# Power.net
KiCad netlist of a schematic drawn in Altium Designer
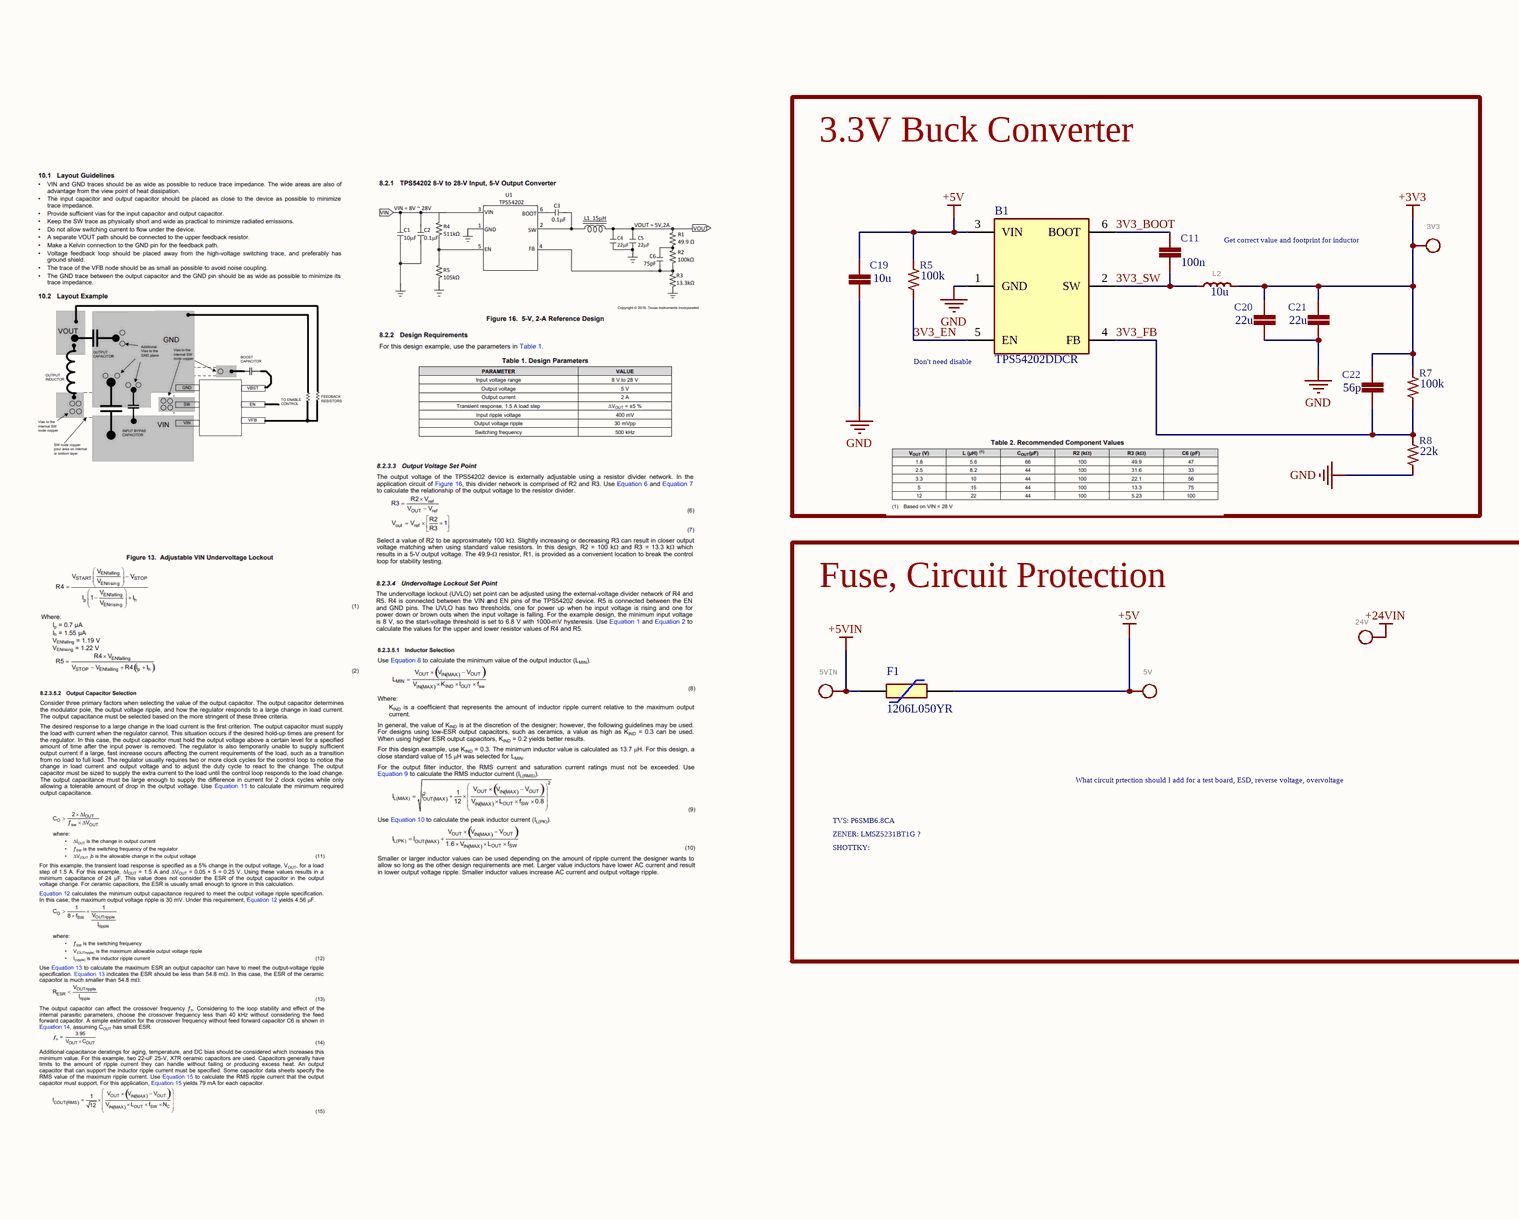
[diagram p0: Power.SchDoc, left]
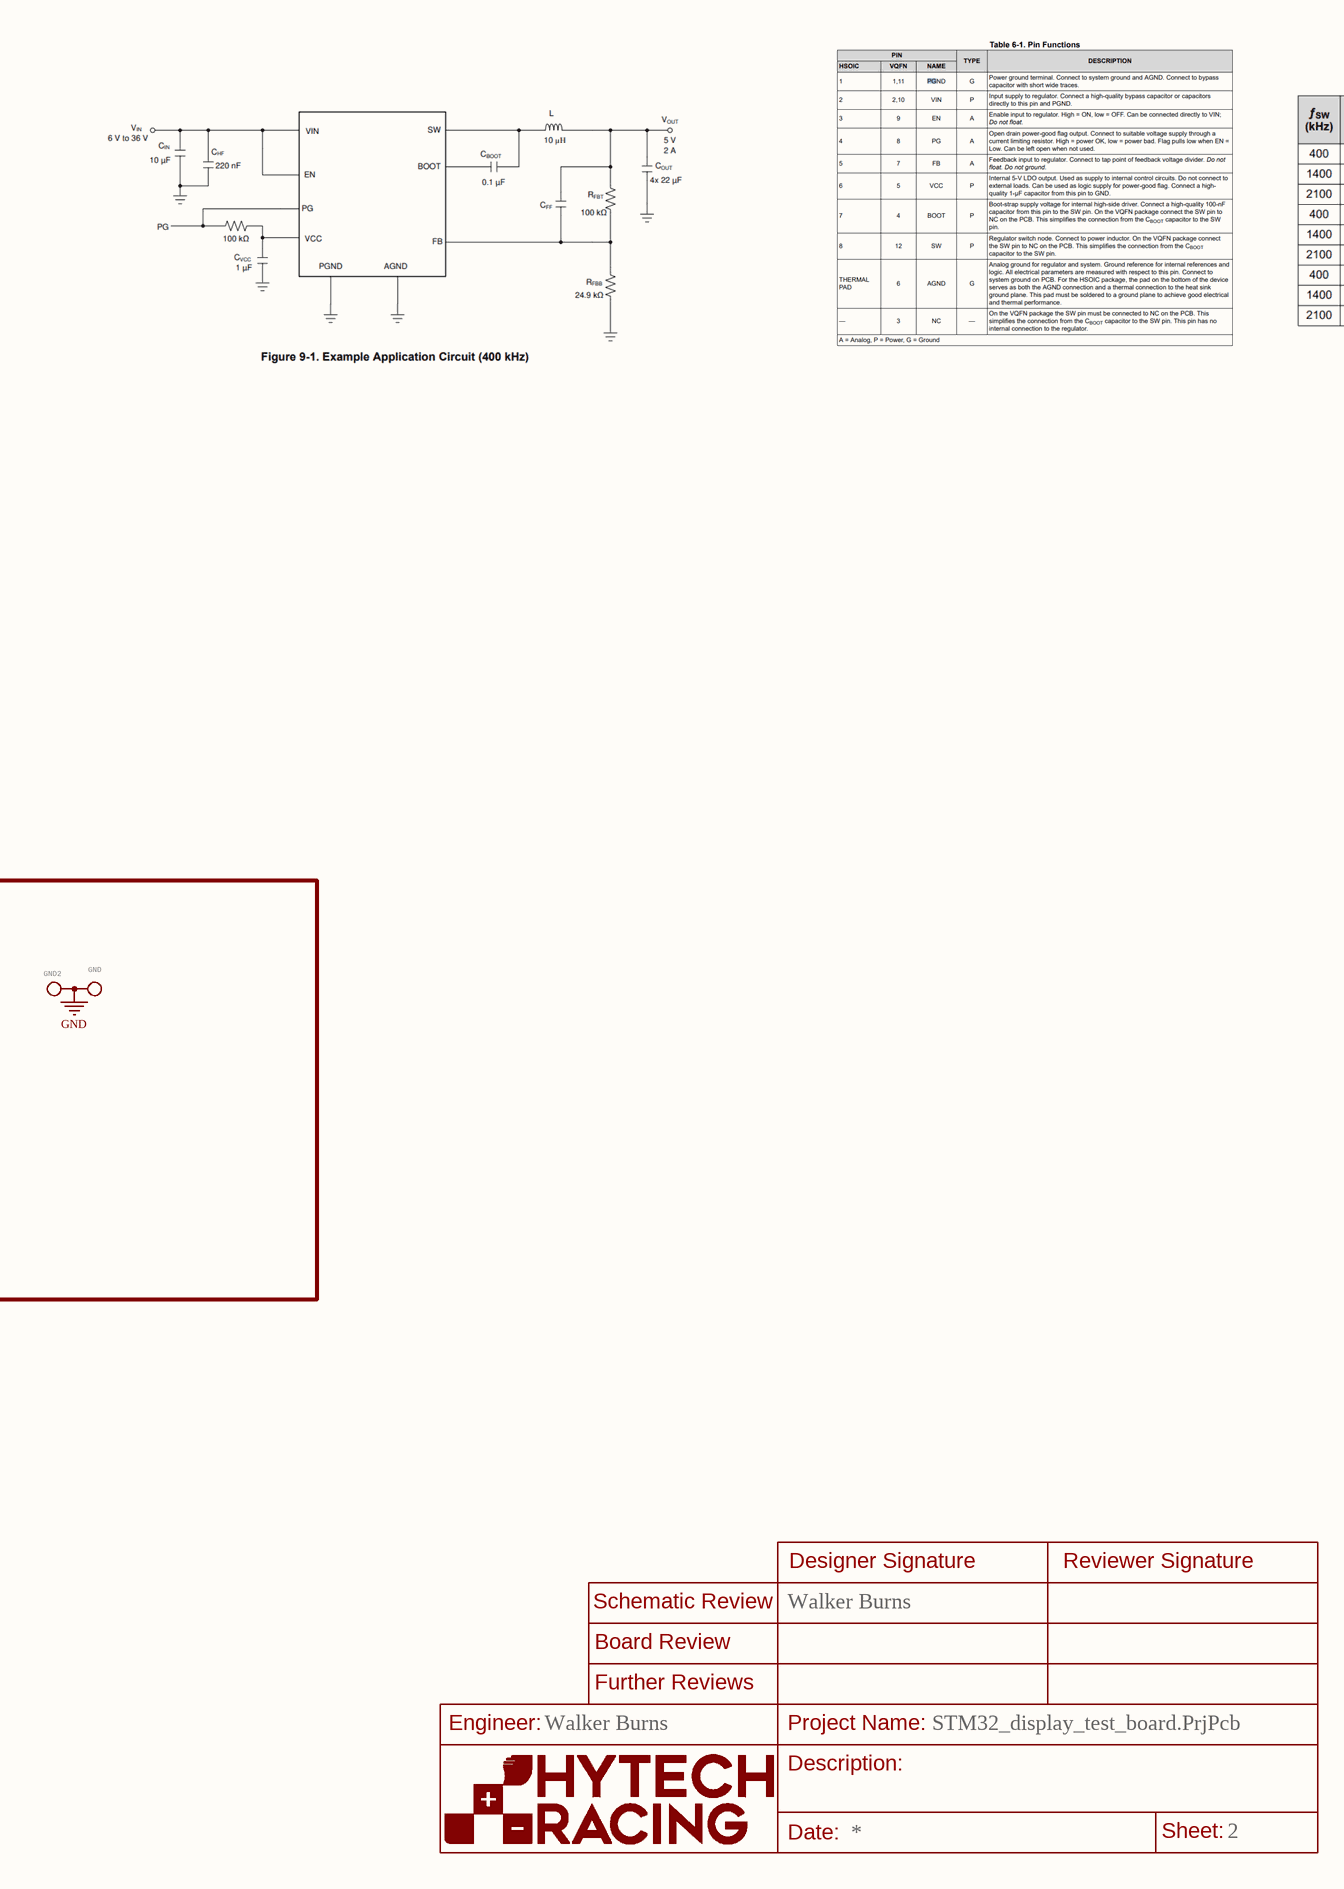
[diagram p1: Power.SchDoc, middle]
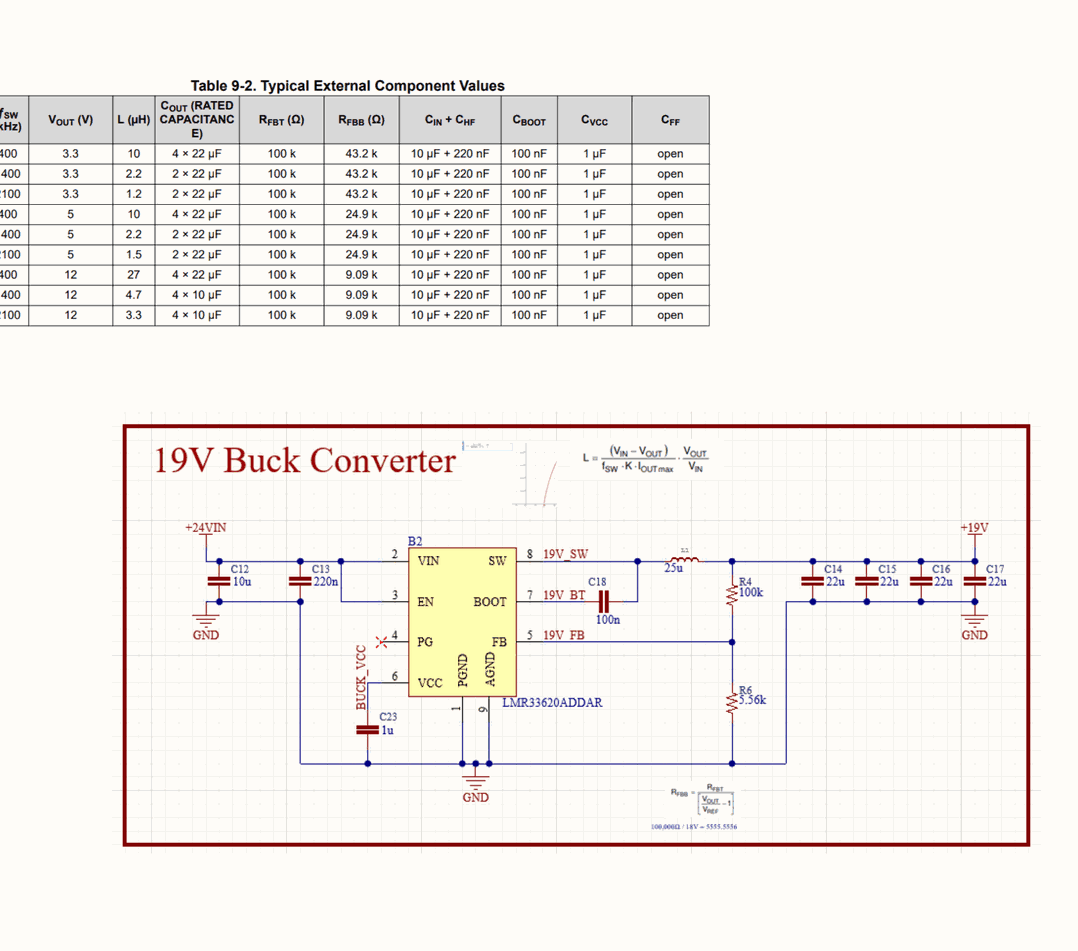
[diagram p2: Power.SchDoc, right]

(export (version "E")
  (design (tool "Eeschema 10.0.6"))
  (components
    (comp (ref "3V3")
      (value "Test Point for Probing")
      (footprint "5015")
      (fields (field (name "MANUFACTURER") "Keystone Electronics") (field (name "MPN") "5015"))
      (libsource (lib "HyTechDevices") (part "TEST_POINT"))
    )
    (comp (ref "5V")
      (value "Test Point for Probing")
      (footprint "5015")
      (fields (field (name "MANUFACTURER") "Keystone Electronics") (field (name "MPN") "5015"))
      (libsource (lib "HyTechDevices") (part "TEST_POINT"))
    )
    (comp (ref "5VIN")
      (value "Test Point for Probing")
      (footprint "5015")
      (fields (field (name "MANUFACTURER") "Keystone Electronics") (field (name "MPN") "5015"))
      (libsource (lib "HyTechDevices") (part "TEST_POINT"))
    )
    (comp (ref "24V")
      (value "Test Point for Probing")
      (footprint "5015")
      (fields (field (name "MANUFACTURER") "Keystone Electronics") (field (name "MPN") "5015"))
      (libsource (lib "HyTechDevices") (part "TEST_POINT"))
    )
    (comp (ref "B1")
      (value "TPS54202DDCR")
      (footprint "SOT-23-6")
      (description "4.5V to 28V Input, 2A Output, EMI Friendly Synchronous Step-Down Converter")
      (fields (field (name "MOUSER PART NUMBER") "595-TPS54202DDCR"))
      (libsource (lib "HyTechDevices") (part "TPS54202DDCR"))
    )
    (comp (ref "C11")
      (value "100n")
      (footprint "0402_CAP")
      (fields
        (field (name "MANUFACTURER") "Yageo")
        (field (name "MPN") "CC0603KRX7R0BB104")
        (field (name "TOLERANCE") "10%")
      )
      (libsource (lib "HyTechDevices") (part "CAPACITOR_?_*0402"))
    )
    (comp (ref "C19")
      (value "10u")
      (footprint "0805-CAP")
      (fields
        (field (name "MANUFACTURER") "KEMET")
        (field (name "MPN") "C0805C224K1RACTU")
        (field (name "TOLERANCE") "10%")
      )
      (libsource (lib "HyTechDevices") (part "CAPACITOR_?_*0805"))
    )
    (comp (ref "C20")
      (value "22u")
      (footprint "1206-CAP")
      (fields
        (field (name "MANUFACTURER") "AVX Corporation")
        (field (name "MPN") "12061C225K4T2A")
        (field (name "TOLERANCE") "10%")
      )
      (libsource (lib "HyTechDevices") (part "CAPACITOR_?_*1206"))
    )
    (comp (ref "C21")
      (value "22u")
      (footprint "1206-CAP")
      (fields
        (field (name "MANUFACTURER") "AVX Corporation")
        (field (name "MPN") "12061C225K4T2A")
        (field (name "TOLERANCE") "10%")
      )
      (libsource (lib "HyTechDevices") (part "CAPACITOR_?_*1206"))
    )
    (comp (ref "C22")
      (value "56p")
      (footprint "1206-CAP")
      (fields
        (field (name "MANUFACTURER") "AVX Corporation")
        (field (name "MPN") "12061C225K4T2A")
        (field (name "TOLERANCE") "10%")
      )
      (libsource (lib "HyTechDevices") (part "CAPACITOR_?_*1206"))
    )
    (comp (ref "F1")
      (value "1206L050YR")
      (footprint "1206-FUSE")
      (description "Resettable POLYFUSE 100A 6V Littelfuse 0.5A Surface Mount Resettable Fuse, 6 V dc")
      (fields (field (name "MOUSER PART NUMBER") "576-1206L050YR"))
      (libsource (lib "HyTechDevices") (part "FUSE_RESETTABLE_1206"))
    )
    (comp (ref "FRAME2")
      (value "HyTech Racing Frame (ANSI Size A)  Prints on US Letter Landscape 8.5\" by 11\"   Fill Engineer/Description Fields with Text using the following settings:  Size: 0.1  Ratio: 8%  Line Distance: 50%  Font: Proportional  Layer: 94 Symbol")
      (fields (field (name "LIBRARYNAME") "HyTechFrames"))
      (libsource (lib "HyTechFrames") (part "FRAME"))
    )
    (comp (ref "GND")
      (value "Test Point for Probing")
      (footprint "5015")
      (fields (field (name "MANUFACTURER") "Keystone Electronics") (field (name "MPN") "5015"))
      (libsource (lib "HyTechDevices") (part "TEST_POINT"))
    )
    (comp (ref "GND2")
      (value "Test Point for Probing")
      (footprint "5015")
      (fields (field (name "MANUFACTURER") "Keystone Electronics") (field (name "MPN") "5015"))
      (libsource (lib "HyTechDevices") (part "TEST_POINT"))
    )
    (comp (ref "L2")
      (value "10u")
      (footprint "1210_IND")
      (fields
        (field (name "MANUFACTURER") "Wurth Elektronik")
        (field (name "MPN") "74437349560")
        (field (name "TOLERANCE") "20%")
      )
      (libsource (lib "HyTechDevices") (part "INDUCTOR_1210"))
    )
    (comp (ref "R5")
      (value "100k")
      (footprint "0603-RES")
      (fields
        (field (name "MANUFACTURER") "Yageo")
        (field (name "MPN") "RC0603FR-070RL")
        (field (name "POWER") "0.1W")
      )
      (libsource (lib "HyTechDevices") (part "RESISTOR_?_*0603"))
    )
    (comp (ref "R7")
      (value "100k")
      (footprint "0603-RES")
      (fields
        (field (name "MANUFACTURER") "Yageo")
        (field (name "MPN") "RC0603FR-070RL")
        (field (name "POWER") "0.1W")
      )
      (libsource (lib "HyTechDevices") (part "RESISTOR_?_*0603"))
    )
    (comp (ref "R8")
      (value "22k")
      (footprint "0603-RES")
      (fields
        (field (name "MANUFACTURER") "Yageo")
        (field (name "MPN") "RC0603FR-070RL")
        (field (name "POWER") "0.1W")
      )
      (libsource (lib "HyTechDevices") (part "RESISTOR_?_*0603"))
    )
  )
  (nets
    (net (code "1") (name "+3V3") (class "Default")
      (node (ref "3V3") (pin "1") (pinfunction "1_1") (pintype "passive"))
      (node (ref "C20") (pin "1") (pinfunction "1_1") (pintype "passive"))
      (node (ref "C21") (pin "1") (pinfunction "1_1") (pintype "passive"))
      (node (ref "C22") (pin "1") (pinfunction "1_1") (pintype "passive"))
      (node (ref "L2") (pin "2") (pinfunction "2_2") (pintype "passive"))
      (node (ref "R7") (pin "1") (pinfunction "1_1") (pintype "passive"))
    )
    (net (code "2") (name "+5V") (class "Default")
      (node (ref "5V") (pin "1") (pinfunction "1_1") (pintype "passive"))
      (node (ref "B1") (pin "3") (pinfunction "VIN_3") (pintype "passive"))
      (node (ref "C19") (pin "1") (pinfunction "1_1") (pintype "passive"))
      (node (ref "F1") (pin "2") (pinfunction "2_2") (pintype "passive"))
      (node (ref "R5") (pin "1") (pinfunction "1_1") (pintype "passive"))
    )
    (net (code "3") (name "+5VIN") (class "Default")
      (node (ref "5VIN") (pin "1") (pinfunction "1_1") (pintype "passive"))
      (node (ref "F1") (pin "1") (pinfunction "1_1") (pintype "passive"))
    )
    (net (code "4") (name "+24VIN") (class "Default")
      (node (ref "24V") (pin "1") (pinfunction "1_1") (pintype "passive"))
    )
    (net (code "5") (name "/3V3_BOOT") (class "Default")
      (node (ref "B1") (pin "6") (pinfunction "BOOT_6") (pintype "passive"))
      (node (ref "C11") (pin "2") (pinfunction "2_2") (pintype "passive"))
    )
    (net (code "6") (name "/3V3_EN") (class "Default")
      (node (ref "B1") (pin "5") (pinfunction "EN_5") (pintype "power_in"))
      (node (ref "R5") (pin "2") (pinfunction "2_2") (pintype "passive"))
    )
    (net (code "7") (name "/3V3_FB") (class "Default")
      (node (ref "B1") (pin "4") (pinfunction "FB_4") (pintype "passive"))
      (node (ref "C22") (pin "2") (pinfunction "2_2") (pintype "passive"))
      (node (ref "R7") (pin "2") (pinfunction "2_2") (pintype "passive"))
      (node (ref "R8") (pin "1") (pinfunction "1_1") (pintype "passive"))
    )
    (net (code "8") (name "/3V3_SW") (class "Default")
      (node (ref "B1") (pin "2") (pinfunction "SW_2") (pintype "passive"))
      (node (ref "C11") (pin "1") (pinfunction "1_1") (pintype "passive"))
      (node (ref "L2") (pin "1") (pinfunction "1_1") (pintype "passive"))
    )
    (net (code "9") (name "GND") (class "Default")
      (node (ref "B1") (pin "1") (pinfunction "GND_1") (pintype "passive"))
      (node (ref "C19") (pin "2") (pinfunction "2_2") (pintype "passive"))
      (node (ref "C20") (pin "2") (pinfunction "2_2") (pintype "passive"))
      (node (ref "C21") (pin "2") (pinfunction "2_2") (pintype "passive"))
      (node (ref "GND") (pin "1") (pinfunction "1_1") (pintype "passive"))
      (node (ref "GND2") (pin "1") (pinfunction "1_1") (pintype "passive"))
      (node (ref "R8") (pin "2") (pinfunction "2_2") (pintype "passive"))
    )
  )
)
